# DigitalClockSegment.net
KiCad netlist of a schematic drawn in EAGLE
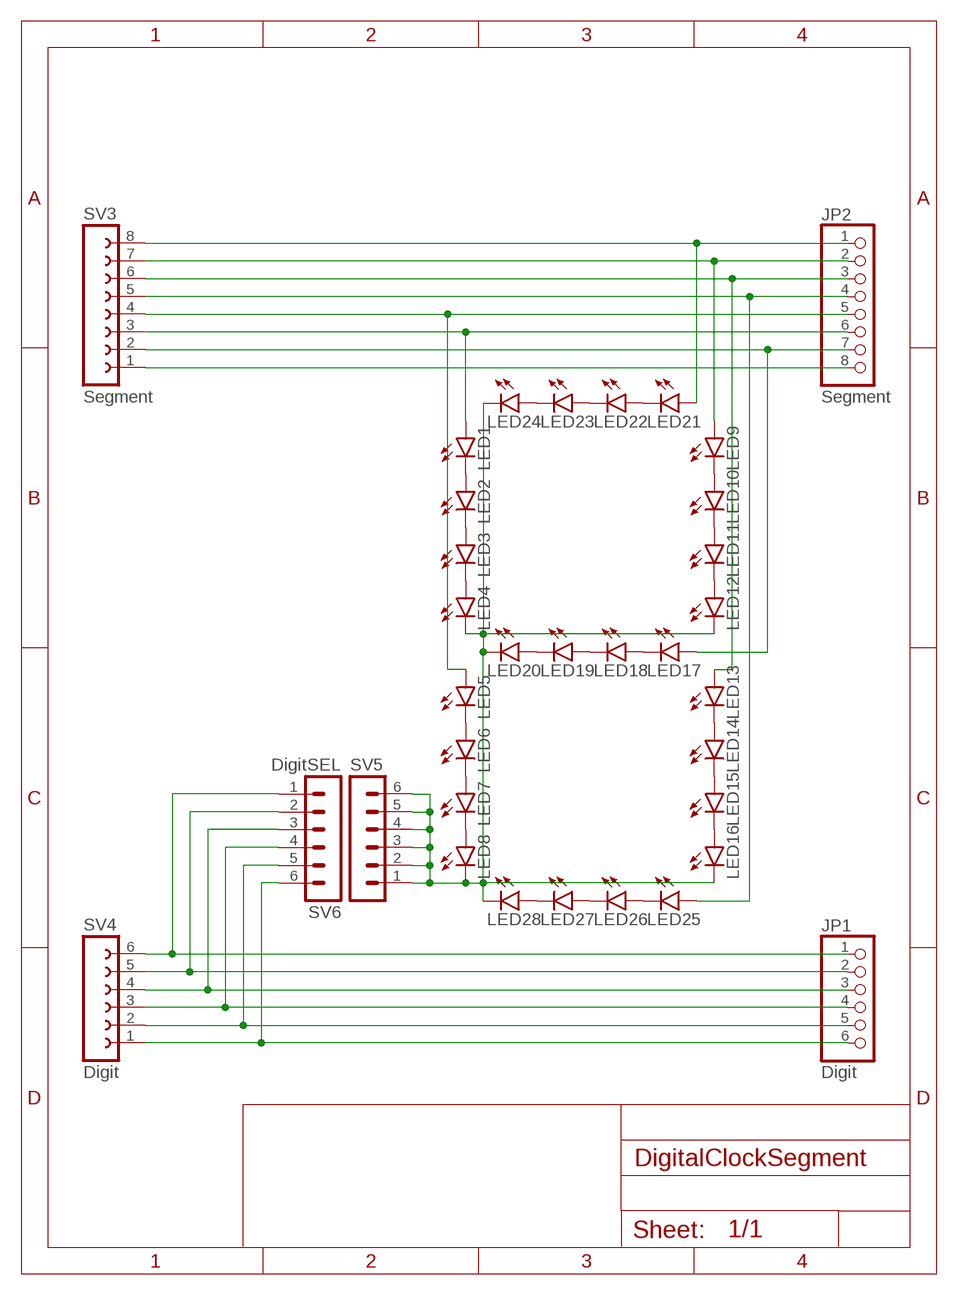
[diagram p0: schematic, sheet 1]

(export (version "E")
  (design (tool "Eeschema 10.0.6"))
  (components
    (comp (ref "JP1")
      (value "Digit")
      (footprint "eagle-import:1X06_90")
      (libsource (lib "eagle-import") (part "PINHD-1X6/90"))
    )
    (comp (ref "JP2")
      (value "Segment")
      (footprint "eagle-import:1X08_90")
      (libsource (lib "eagle-import") (part "PINHD-1X8/90"))
    )
    (comp (ref "LED1")
      (value "LED5MM")
      (footprint "eagle-import:LED5MM")
      (libsource (lib "eagle-import") (part "LED5MM"))
    )
    (comp (ref "LED2")
      (value "LED5MM")
      (footprint "eagle-import:LED5MM")
      (libsource (lib "eagle-import") (part "LED5MM"))
    )
    (comp (ref "LED3")
      (value "LED5MM")
      (footprint "eagle-import:LED5MM")
      (libsource (lib "eagle-import") (part "LED5MM"))
    )
    (comp (ref "LED4")
      (value "LED5MM")
      (footprint "eagle-import:LED5MM")
      (libsource (lib "eagle-import") (part "LED5MM"))
    )
    (comp (ref "LED5")
      (value "LED5MM")
      (footprint "eagle-import:LED5MM")
      (libsource (lib "eagle-import") (part "LED5MM"))
    )
    (comp (ref "LED6")
      (value "LED5MM")
      (footprint "eagle-import:LED5MM")
      (libsource (lib "eagle-import") (part "LED5MM"))
    )
    (comp (ref "LED7")
      (value "LED5MM")
      (footprint "eagle-import:LED5MM")
      (libsource (lib "eagle-import") (part "LED5MM"))
    )
    (comp (ref "LED8")
      (value "LED5MM")
      (footprint "eagle-import:LED5MM")
      (libsource (lib "eagle-import") (part "LED5MM"))
    )
    (comp (ref "LED9")
      (value "LED5MM")
      (footprint "eagle-import:LED5MM")
      (libsource (lib "eagle-import") (part "LED5MM"))
    )
    (comp (ref "LED10")
      (value "LED5MM")
      (footprint "eagle-import:LED5MM")
      (libsource (lib "eagle-import") (part "LED5MM"))
    )
    (comp (ref "LED11")
      (value "LED5MM")
      (footprint "eagle-import:LED5MM")
      (libsource (lib "eagle-import") (part "LED5MM"))
    )
    (comp (ref "LED12")
      (value "LED5MM")
      (footprint "eagle-import:LED5MM")
      (libsource (lib "eagle-import") (part "LED5MM"))
    )
    (comp (ref "LED13")
      (value "LED5MM")
      (footprint "eagle-import:LED5MM")
      (libsource (lib "eagle-import") (part "LED5MM"))
    )
    (comp (ref "LED14")
      (value "LED5MM")
      (footprint "eagle-import:LED5MM")
      (libsource (lib "eagle-import") (part "LED5MM"))
    )
    (comp (ref "LED15")
      (value "LED5MM")
      (footprint "eagle-import:LED5MM")
      (libsource (lib "eagle-import") (part "LED5MM"))
    )
    (comp (ref "LED16")
      (value "LED5MM")
      (footprint "eagle-import:LED5MM")
      (libsource (lib "eagle-import") (part "LED5MM"))
    )
    (comp (ref "LED17")
      (value "LED5MM")
      (footprint "eagle-import:LED5MM")
      (libsource (lib "eagle-import") (part "LED5MM"))
    )
    (comp (ref "LED18")
      (value "LED5MM")
      (footprint "eagle-import:LED5MM")
      (libsource (lib "eagle-import") (part "LED5MM"))
    )
    (comp (ref "LED19")
      (value "LED5MM")
      (footprint "eagle-import:LED5MM")
      (libsource (lib "eagle-import") (part "LED5MM"))
    )
    (comp (ref "LED20")
      (value "LED5MM")
      (footprint "eagle-import:LED5MM")
      (libsource (lib "eagle-import") (part "LED5MM"))
    )
    (comp (ref "LED21")
      (value "LED5MM")
      (footprint "eagle-import:LED5MM")
      (libsource (lib "eagle-import") (part "LED5MM"))
    )
    (comp (ref "LED22")
      (value "LED5MM")
      (footprint "eagle-import:LED5MM")
      (libsource (lib "eagle-import") (part "LED5MM"))
    )
    (comp (ref "LED23")
      (value "LED5MM")
      (footprint "eagle-import:LED5MM")
      (libsource (lib "eagle-import") (part "LED5MM"))
    )
    (comp (ref "LED24")
      (value "LED5MM")
      (footprint "eagle-import:LED5MM")
      (libsource (lib "eagle-import") (part "LED5MM"))
    )
    (comp (ref "LED25")
      (value "LED5MM")
      (footprint "eagle-import:LED5MM")
      (libsource (lib "eagle-import") (part "LED5MM"))
    )
    (comp (ref "LED26")
      (value "LED5MM")
      (footprint "eagle-import:LED5MM")
      (libsource (lib "eagle-import") (part "LED5MM"))
    )
    (comp (ref "LED27")
      (value "LED5MM")
      (footprint "eagle-import:LED5MM")
      (libsource (lib "eagle-import") (part "LED5MM"))
    )
    (comp (ref "LED28")
      (value "LED5MM")
      (footprint "eagle-import:LED5MM")
      (libsource (lib "eagle-import") (part "LED5MM"))
    )
    (comp (ref "SV3")
      (value "Segment")
      (footprint "eagle-import:FE08W")
      (libsource (lib "eagle-import") (part "FE08W"))
    )
    (comp (ref "SV4")
      (value "Digit")
      (footprint "eagle-import:FE06W")
      (libsource (lib "eagle-import") (part "FE06W"))
    )
    (comp (ref "SV5")
      (value "MA06-1")
      (footprint "eagle-import:MA06-1")
      (libsource (lib "eagle-import") (part "MA06-1"))
    )
    (comp (ref "SV6")
      (value "DigitSEL")
      (footprint "eagle-import:MA06-1")
      (libsource (lib "eagle-import") (part "MA06-1"))
    )
  )
  (nets
    (net (code "1") (name "Net-(JP1-Pad1)") (class "Default")
      (node (ref "JP1") (pin "1") (pinfunction "1_1") (pintype "passive"))
      (node (ref "SV4") (pin "6") (pinfunction "6_6") (pintype "passive"))
      (node (ref "SV6") (pin "1") (pinfunction "1_1") (pintype "passive"))
    )
    (net (code "2") (name "Net-(JP1-Pad2)") (class "Default")
      (node (ref "JP1") (pin "2") (pinfunction "2_2") (pintype "passive"))
      (node (ref "SV4") (pin "5") (pinfunction "5_5") (pintype "passive"))
      (node (ref "SV6") (pin "2") (pinfunction "2_2") (pintype "passive"))
    )
    (net (code "3") (name "Net-(JP1-Pad3)") (class "Default")
      (node (ref "JP1") (pin "3") (pinfunction "3_3") (pintype "passive"))
      (node (ref "SV4") (pin "4") (pinfunction "4_4") (pintype "passive"))
      (node (ref "SV6") (pin "3") (pinfunction "3_3") (pintype "passive"))
    )
    (net (code "4") (name "Net-(JP1-Pad4)") (class "Default")
      (node (ref "JP1") (pin "4") (pinfunction "4_4") (pintype "passive"))
      (node (ref "SV4") (pin "3") (pinfunction "3_3") (pintype "passive"))
      (node (ref "SV6") (pin "4") (pinfunction "4_4") (pintype "passive"))
    )
    (net (code "5") (name "Net-(JP1-Pad5)") (class "Default")
      (node (ref "JP1") (pin "5") (pinfunction "5_5") (pintype "passive"))
      (node (ref "SV4") (pin "2") (pinfunction "2_2") (pintype "passive"))
      (node (ref "SV6") (pin "5") (pinfunction "5_5") (pintype "passive"))
    )
    (net (code "6") (name "Net-(JP1-Pad6)") (class "Default")
      (node (ref "JP1") (pin "6") (pinfunction "6_6") (pintype "passive"))
      (node (ref "SV4") (pin "1") (pinfunction "1_1") (pintype "passive"))
      (node (ref "SV6") (pin "6") (pinfunction "6_6") (pintype "passive"))
    )
    (net (code "7") (name "Net-(JP2-Pad1)") (class "Default")
      (node (ref "JP2") (pin "1") (pinfunction "1_1") (pintype "passive"))
      (node (ref "LED21") (pin "A") (pinfunction "A_A") (pintype "passive"))
      (node (ref "SV3") (pin "8") (pinfunction "8_8") (pintype "passive"))
    )
    (net (code "8") (name "Net-(JP2-Pad2)") (class "Default")
      (node (ref "JP2") (pin "2") (pinfunction "2_2") (pintype "passive"))
      (node (ref "LED9") (pin "A") (pinfunction "A_A") (pintype "passive"))
      (node (ref "SV3") (pin "7") (pinfunction "7_7") (pintype "passive"))
    )
    (net (code "9") (name "Net-(JP2-Pad3)") (class "Default")
      (node (ref "JP2") (pin "3") (pinfunction "3_3") (pintype "passive"))
      (node (ref "LED13") (pin "A") (pinfunction "A_A") (pintype "passive"))
      (node (ref "SV3") (pin "6") (pinfunction "6_6") (pintype "passive"))
    )
    (net (code "10") (name "Net-(JP2-Pad4)") (class "Default")
      (node (ref "JP2") (pin "4") (pinfunction "4_4") (pintype "passive"))
      (node (ref "LED25") (pin "A") (pinfunction "A_A") (pintype "passive"))
      (node (ref "SV3") (pin "5") (pinfunction "5_5") (pintype "passive"))
    )
    (net (code "11") (name "Net-(JP2-Pad5)") (class "Default")
      (node (ref "JP2") (pin "5") (pinfunction "5_5") (pintype "passive"))
      (node (ref "LED5") (pin "A") (pinfunction "A_A") (pintype "passive"))
      (node (ref "SV3") (pin "4") (pinfunction "4_4") (pintype "passive"))
    )
    (net (code "12") (name "Net-(JP2-Pad6)") (class "Default")
      (node (ref "JP2") (pin "6") (pinfunction "6_6") (pintype "passive"))
      (node (ref "LED1") (pin "A") (pinfunction "A_A") (pintype "passive"))
      (node (ref "SV3") (pin "3") (pinfunction "3_3") (pintype "passive"))
    )
    (net (code "13") (name "Net-(JP2-Pad7)") (class "Default")
      (node (ref "JP2") (pin "7") (pinfunction "7_7") (pintype "passive"))
      (node (ref "LED17") (pin "A") (pinfunction "A_A") (pintype "passive"))
      (node (ref "SV3") (pin "2") (pinfunction "2_2") (pintype "passive"))
    )
    (net (code "14") (name "Net-(JP2-Pad8)") (class "Default")
      (node (ref "JP2") (pin "8") (pinfunction "8_8") (pintype "passive"))
      (node (ref "SV3") (pin "1") (pinfunction "1_1") (pintype "passive"))
    )
    (net (code "15") (name "Net-(LED1-C)") (class "Default")
      (node (ref "LED1") (pin "K") (pinfunction "C_K") (pintype "passive"))
      (node (ref "LED2") (pin "A") (pinfunction "A_A") (pintype "passive"))
    )
    (net (code "16") (name "Net-(LED2-C)") (class "Default")
      (node (ref "LED2") (pin "K") (pinfunction "C_K") (pintype "passive"))
      (node (ref "LED3") (pin "A") (pinfunction "A_A") (pintype "passive"))
    )
    (net (code "17") (name "Net-(LED3-C)") (class "Default")
      (node (ref "LED3") (pin "K") (pinfunction "C_K") (pintype "passive"))
      (node (ref "LED4") (pin "A") (pinfunction "A_A") (pintype "passive"))
    )
    (net (code "18") (name "Net-(LED5-C)") (class "Default")
      (node (ref "LED5") (pin "K") (pinfunction "C_K") (pintype "passive"))
      (node (ref "LED6") (pin "A") (pinfunction "A_A") (pintype "passive"))
    )
    (net (code "19") (name "Net-(LED6-C)") (class "Default")
      (node (ref "LED6") (pin "K") (pinfunction "C_K") (pintype "passive"))
      (node (ref "LED7") (pin "A") (pinfunction "A_A") (pintype "passive"))
    )
    (net (code "20") (name "Net-(LED7-C)") (class "Default")
      (node (ref "LED7") (pin "K") (pinfunction "C_K") (pintype "passive"))
      (node (ref "LED8") (pin "A") (pinfunction "A_A") (pintype "passive"))
    )
    (net (code "21") (name "Net-(LED9-C)") (class "Default")
      (node (ref "LED10") (pin "A") (pinfunction "A_A") (pintype "passive"))
      (node (ref "LED9") (pin "K") (pinfunction "C_K") (pintype "passive"))
    )
    (net (code "22") (name "Net-(LED10-C)") (class "Default")
      (node (ref "LED10") (pin "K") (pinfunction "C_K") (pintype "passive"))
      (node (ref "LED11") (pin "A") (pinfunction "A_A") (pintype "passive"))
    )
    (net (code "23") (name "Net-(LED11-C)") (class "Default")
      (node (ref "LED11") (pin "K") (pinfunction "C_K") (pintype "passive"))
      (node (ref "LED12") (pin "A") (pinfunction "A_A") (pintype "passive"))
    )
    (net (code "24") (name "Net-(LED12-C)") (class "Default")
      (node (ref "LED12") (pin "K") (pinfunction "C_K") (pintype "passive"))
      (node (ref "LED16") (pin "K") (pinfunction "C_K") (pintype "passive"))
      (node (ref "LED20") (pin "K") (pinfunction "C_K") (pintype "passive"))
      (node (ref "LED24") (pin "K") (pinfunction "C_K") (pintype "passive"))
      (node (ref "LED28") (pin "K") (pinfunction "C_K") (pintype "passive"))
      (node (ref "LED4") (pin "K") (pinfunction "C_K") (pintype "passive"))
      (node (ref "LED8") (pin "K") (pinfunction "C_K") (pintype "passive"))
      (node (ref "SV5") (pin "1") (pinfunction "1_1") (pintype "passive"))
      (node (ref "SV5") (pin "2") (pinfunction "2_2") (pintype "passive"))
      (node (ref "SV5") (pin "3") (pinfunction "3_3") (pintype "passive"))
      (node (ref "SV5") (pin "4") (pinfunction "4_4") (pintype "passive"))
      (node (ref "SV5") (pin "5") (pinfunction "5_5") (pintype "passive"))
      (node (ref "SV5") (pin "6") (pinfunction "6_6") (pintype "passive"))
    )
    (net (code "25") (name "Net-(LED13-C)") (class "Default")
      (node (ref "LED13") (pin "K") (pinfunction "C_K") (pintype "passive"))
      (node (ref "LED14") (pin "A") (pinfunction "A_A") (pintype "passive"))
    )
    (net (code "26") (name "Net-(LED14-C)") (class "Default")
      (node (ref "LED14") (pin "K") (pinfunction "C_K") (pintype "passive"))
      (node (ref "LED15") (pin "A") (pinfunction "A_A") (pintype "passive"))
    )
    (net (code "27") (name "Net-(LED15-C)") (class "Default")
      (node (ref "LED15") (pin "K") (pinfunction "C_K") (pintype "passive"))
      (node (ref "LED16") (pin "A") (pinfunction "A_A") (pintype "passive"))
    )
    (net (code "28") (name "Net-(LED17-C)") (class "Default")
      (node (ref "LED17") (pin "K") (pinfunction "C_K") (pintype "passive"))
      (node (ref "LED18") (pin "A") (pinfunction "A_A") (pintype "passive"))
    )
    (net (code "29") (name "Net-(LED18-C)") (class "Default")
      (node (ref "LED18") (pin "K") (pinfunction "C_K") (pintype "passive"))
      (node (ref "LED19") (pin "A") (pinfunction "A_A") (pintype "passive"))
    )
    (net (code "30") (name "Net-(LED19-C)") (class "Default")
      (node (ref "LED19") (pin "K") (pinfunction "C_K") (pintype "passive"))
      (node (ref "LED20") (pin "A") (pinfunction "A_A") (pintype "passive"))
    )
    (net (code "31") (name "Net-(LED21-C)") (class "Default")
      (node (ref "LED21") (pin "K") (pinfunction "C_K") (pintype "passive"))
      (node (ref "LED22") (pin "A") (pinfunction "A_A") (pintype "passive"))
    )
    (net (code "32") (name "Net-(LED22-C)") (class "Default")
      (node (ref "LED22") (pin "K") (pinfunction "C_K") (pintype "passive"))
      (node (ref "LED23") (pin "A") (pinfunction "A_A") (pintype "passive"))
    )
    (net (code "33") (name "Net-(LED23-C)") (class "Default")
      (node (ref "LED23") (pin "K") (pinfunction "C_K") (pintype "passive"))
      (node (ref "LED24") (pin "A") (pinfunction "A_A") (pintype "passive"))
    )
    (net (code "34") (name "Net-(LED25-C)") (class "Default")
      (node (ref "LED25") (pin "K") (pinfunction "C_K") (pintype "passive"))
      (node (ref "LED26") (pin "A") (pinfunction "A_A") (pintype "passive"))
    )
    (net (code "35") (name "Net-(LED26-C)") (class "Default")
      (node (ref "LED26") (pin "K") (pinfunction "C_K") (pintype "passive"))
      (node (ref "LED27") (pin "A") (pinfunction "A_A") (pintype "passive"))
    )
    (net (code "36") (name "Net-(LED27-C)") (class "Default")
      (node (ref "LED27") (pin "K") (pinfunction "C_K") (pintype "passive"))
      (node (ref "LED28") (pin "A") (pinfunction "A_A") (pintype "passive"))
    )
  )
)
